# Digital_Output_B.net
KiCad netlist of a schematic drawn in EAGLE
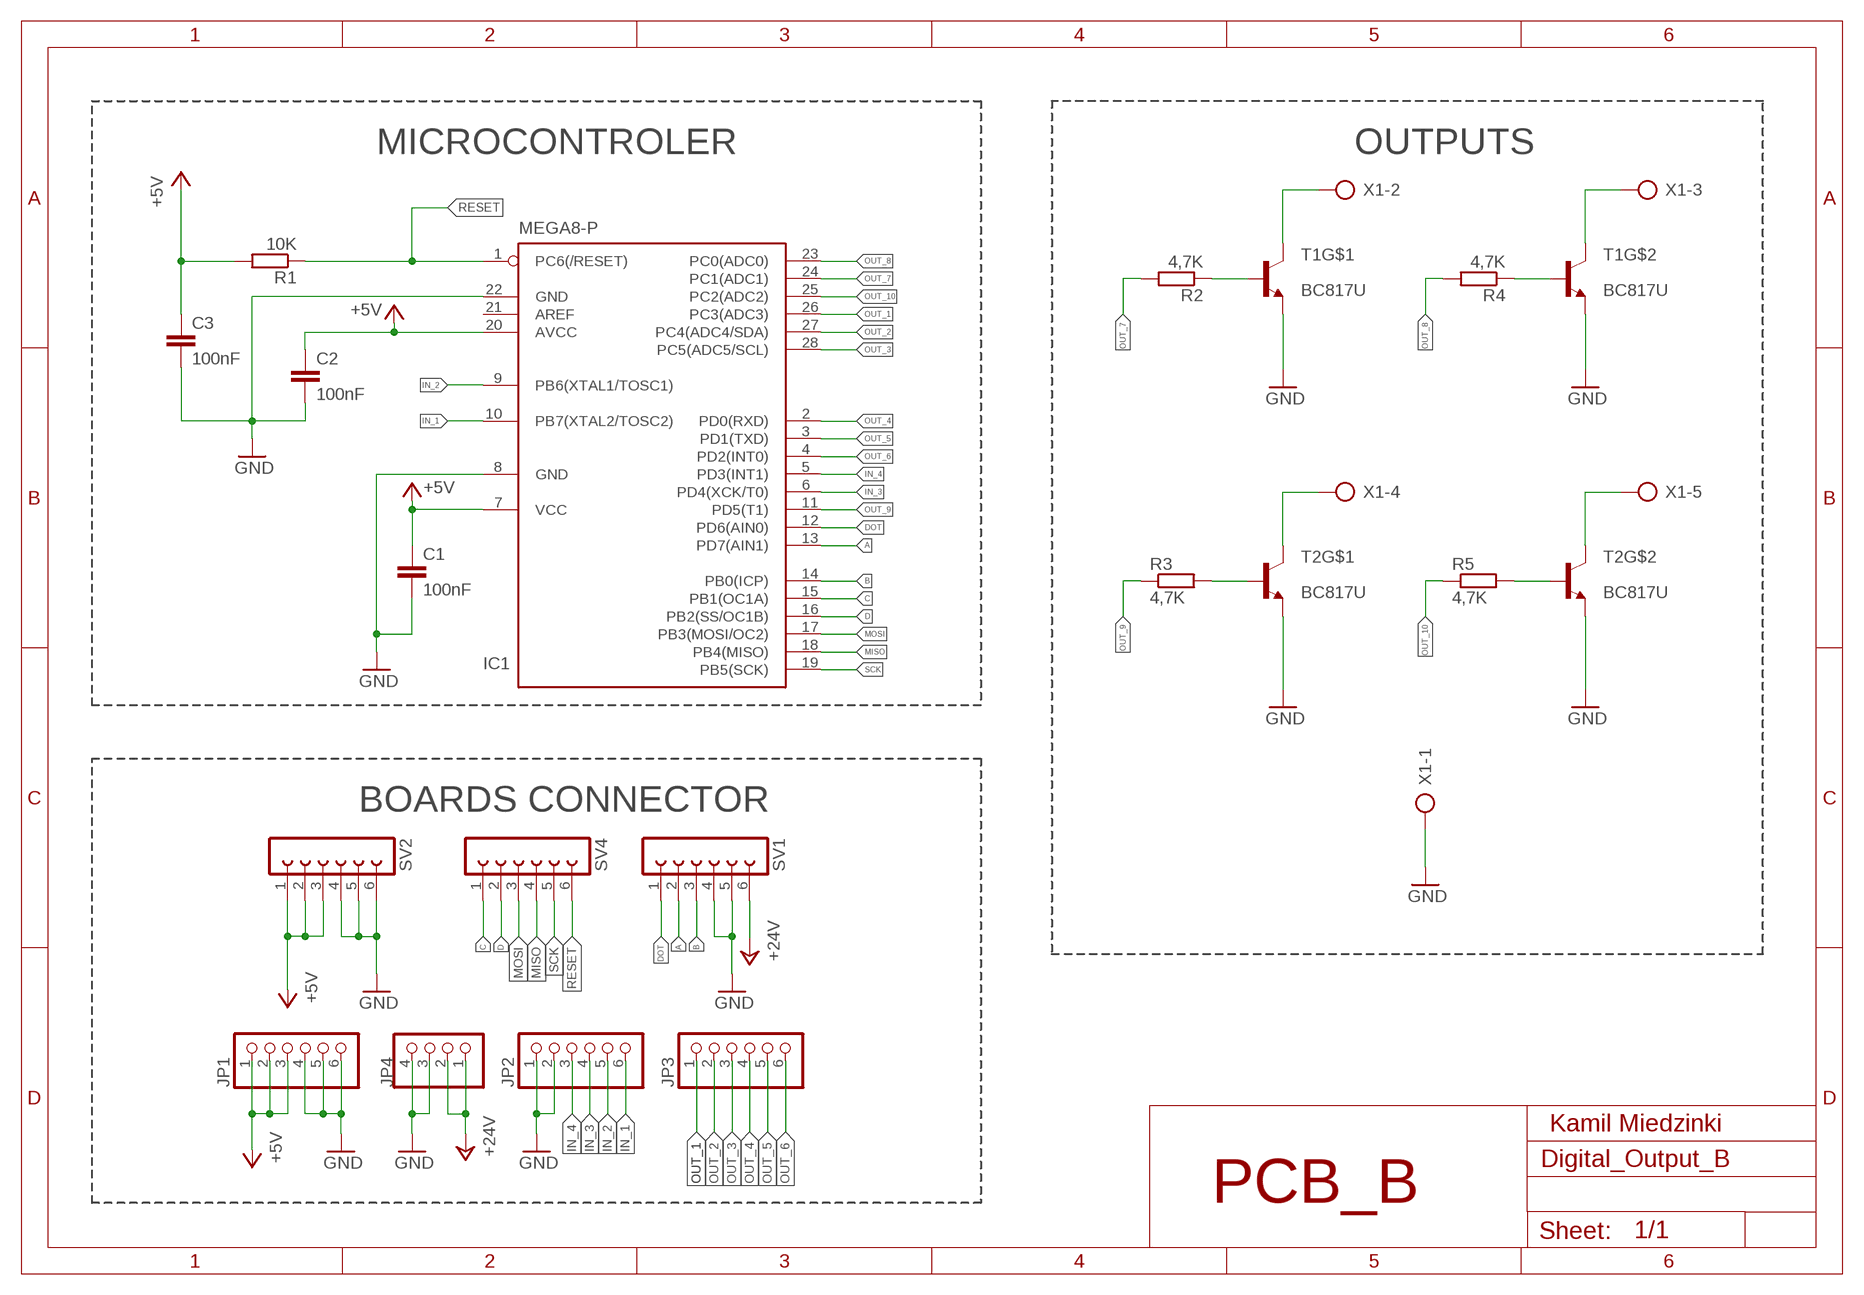
[diagram p0: schematic, sheet 1]

(export (version "E")
  (design (tool "Eeschema 10.0.6"))
  (components
    (comp (ref "C1")
      (value "100nF")
      (footprint "eagle-import:C0805K")
      (libsource (lib "eagle-import") (part "C-EUC0805K"))
    )
    (comp (ref "C2")
      (value "100nF")
      (footprint "eagle-import:C0805K")
      (libsource (lib "eagle-import") (part "C-EUC0805K"))
    )
    (comp (ref "C3")
      (value "100nF")
      (footprint "eagle-import:C0805K")
      (libsource (lib "eagle-import") (part "C-EUC0805K"))
    )
    (comp (ref "IC1")
      (value "MEGA8-P")
      (footprint "eagle-import:DIL28-3")
      (libsource (lib "eagle-import") (part "MEGA8-P"))
    )
    (comp (ref "JP1")
      (value "PINHD-1X6\"")
      (footprint "eagle-import:1X06H")
      (libsource (lib "eagle-import") (part "PINHD-1X6{dblquote}"))
    )
    (comp (ref "JP2")
      (value "PINHD-1X6\"")
      (footprint "eagle-import:1X06H")
      (libsource (lib "eagle-import") (part "PINHD-1X6{dblquote}"))
    )
    (comp (ref "JP3")
      (value "PINHD-1X6\"")
      (footprint "eagle-import:1X06H")
      (libsource (lib "eagle-import") (part "PINHD-1X6{dblquote}"))
    )
    (comp (ref "JP4")
      (value "PINHD-1X41X04H")
      (footprint "eagle-import:1X04H")
      (libsource (lib "eagle-import") (part "PINHD-1X41X04H"))
    )
    (comp (ref "R1")
      (value "10K")
      (footprint "eagle-import:R0805")
      (libsource (lib "eagle-import") (part "R-EU_R0805"))
    )
    (comp (ref "R2")
      (value "4,7K")
      (footprint "eagle-import:R0805")
      (libsource (lib "eagle-import") (part "R-EU_R0805"))
    )
    (comp (ref "R3")
      (value "4,7K")
      (footprint "eagle-import:R0805")
      (libsource (lib "eagle-import") (part "R-EU_R0805"))
    )
    (comp (ref "R4")
      (value "4,7K")
      (footprint "eagle-import:R0805")
      (libsource (lib "eagle-import") (part "R-EU_R0805"))
    )
    (comp (ref "R5")
      (value "4,7K")
      (footprint "eagle-import:R0805")
      (libsource (lib "eagle-import") (part "R-EU_R0805"))
    )
    (comp (ref "SV1")
      (value "FE06-1")
      (footprint "eagle-import:FE06")
      (libsource (lib "eagle-import") (part "FE06-1"))
    )
    (comp (ref "SV2")
      (value "FE06-1")
      (footprint "eagle-import:FE06")
      (libsource (lib "eagle-import") (part "FE06-1"))
    )
    (comp (ref "SV4")
      (value "FE06-1")
      (footprint "eagle-import:FE06")
      (libsource (lib "eagle-import") (part "FE06-1"))
    )
    (comp (ref "T1")
      (value "BC817U")
      (footprint "eagle-import:INF-SC74")
      (libsource (lib "eagle-import") (part "BC817U"))
    )
    (comp (ref "T2")
      (value "BC817U")
      (footprint "eagle-import:INF-SC74")
      (libsource (lib "eagle-import") (part "BC817U"))
    )
    (comp (ref "X1")
      (value "MKDS_3/5")
      (footprint "eagle-import:MKDS_3_5")
      (libsource (lib "eagle-import") (part "MKDS_3/5"))
    )
  )
  (nets
    (net (code "1") (name "+5V") (class "Default")
      (node (ref "C1") (pin "1") (pinfunction "1_1") (pintype "passive"))
      (node (ref "C2") (pin "1") (pinfunction "1_1") (pintype "passive"))
      (node (ref "C3") (pin "1") (pinfunction "1_1") (pintype "passive"))
      (node (ref "IC1") (pin "20") (pinfunction "AVCC_20") (pintype "power_in"))
      (node (ref "IC1") (pin "7") (pinfunction "VCC_7") (pintype "power_in"))
      (node (ref "JP1") (pin "1") (pinfunction "1_1") (pintype "passive"))
      (node (ref "JP1") (pin "2") (pinfunction "2_2") (pintype "passive"))
      (node (ref "JP1") (pin "3") (pinfunction "3_3") (pintype "passive"))
      (node (ref "R1") (pin "2") (pinfunction "2_2") (pintype "passive"))
      (node (ref "SV2") (pin "1") (pinfunction "1_1") (pintype "passive"))
      (node (ref "SV2") (pin "2") (pinfunction "2_2") (pintype "passive"))
      (node (ref "SV2") (pin "3") (pinfunction "3_3") (pintype "passive"))
    )
    (net (code "2") (name "+24V") (class "Default")
      (node (ref "JP4") (pin "1") (pinfunction "1_1") (pintype "passive"))
      (node (ref "JP4") (pin "2") (pinfunction "2_2") (pintype "passive"))
      (node (ref "SV1") (pin "6") (pinfunction "6_6") (pintype "passive"))
    )
    (net (code "3") (name "A") (class "Default")
      (node (ref "IC1") (pin "13") (pinfunction "PD7(AIN1)_13") (pintype "bidirectional"))
      (node (ref "SV1") (pin "2") (pinfunction "2_2") (pintype "passive"))
    )
    (net (code "4") (name "B") (class "Default")
      (node (ref "IC1") (pin "14") (pinfunction "PB0(ICP)_14") (pintype "bidirectional"))
      (node (ref "SV1") (pin "3") (pinfunction "3_3") (pintype "passive"))
    )
    (net (code "5") (name "C") (class "Default")
      (node (ref "IC1") (pin "15") (pinfunction "PB1(OC1A)_15") (pintype "bidirectional"))
      (node (ref "SV4") (pin "1") (pinfunction "1_1") (pintype "passive"))
    )
    (net (code "6") (name "D") (class "Default")
      (node (ref "IC1") (pin "16") (pinfunction "PB2(SS/OC1B)_16") (pintype "bidirectional"))
      (node (ref "SV4") (pin "2") (pinfunction "2_2") (pintype "passive"))
    )
    (net (code "7") (name "DOT") (class "Default")
      (node (ref "IC1") (pin "12") (pinfunction "PD6(AIN0)_12") (pintype "bidirectional"))
      (node (ref "SV1") (pin "1") (pinfunction "1_1") (pintype "passive"))
    )
    (net (code "8") (name "GND") (class "Default")
      (node (ref "C1") (pin "2") (pinfunction "2_2") (pintype "passive"))
      (node (ref "C2") (pin "2") (pinfunction "2_2") (pintype "passive"))
      (node (ref "C3") (pin "2") (pinfunction "2_2") (pintype "passive"))
      (node (ref "IC1") (pin "22") (pinfunction "GND_22") (pintype "power_in"))
      (node (ref "IC1") (pin "8") (pinfunction "GND_8") (pintype "power_in"))
      (node (ref "JP1") (pin "4") (pinfunction "4_4") (pintype "passive"))
      (node (ref "JP1") (pin "5") (pinfunction "5_5") (pintype "passive"))
      (node (ref "JP1") (pin "6") (pinfunction "6_6") (pintype "passive"))
      (node (ref "JP2") (pin "1") (pinfunction "1_1") (pintype "passive"))
      (node (ref "JP2") (pin "2") (pinfunction "2_2") (pintype "passive"))
      (node (ref "JP4") (pin "3") (pinfunction "3_3") (pintype "passive"))
      (node (ref "JP4") (pin "4") (pinfunction "4_4") (pintype "passive"))
      (node (ref "SV1") (pin "4") (pinfunction "4_4") (pintype "passive"))
      (node (ref "SV1") (pin "5") (pinfunction "5_5") (pintype "passive"))
      (node (ref "SV2") (pin "4") (pinfunction "4_4") (pintype "passive"))
      (node (ref "SV2") (pin "5") (pinfunction "5_5") (pintype "passive"))
      (node (ref "SV2") (pin "6") (pinfunction "6_6") (pintype "passive"))
      (node (ref "T1") (pin "1") (pinfunction "E_1") (pintype "passive"))
      (node (ref "T1") (pin "4") (pinfunction "E_4") (pintype "passive"))
      (node (ref "T2") (pin "1") (pinfunction "E_1") (pintype "passive"))
      (node (ref "T2") (pin "4") (pinfunction "E_4") (pintype "passive"))
      (node (ref "X1") (pin "1") (pinfunction "KL_1") (pintype "passive"))
    )
    (net (code "9") (name "IN_1") (class "Default")
      (node (ref "IC1") (pin "10") (pinfunction "PB7(XTAL2/TOSC2)_10") (pintype "bidirectional"))
      (node (ref "JP2") (pin "6") (pinfunction "6_6") (pintype "passive"))
    )
    (net (code "10") (name "IN_2") (class "Default")
      (node (ref "IC1") (pin "9") (pinfunction "PB6(XTAL1/TOSC1)_9") (pintype "bidirectional"))
      (node (ref "JP2") (pin "5") (pinfunction "5_5") (pintype "passive"))
    )
    (net (code "11") (name "IN_3") (class "Default")
      (node (ref "IC1") (pin "6") (pinfunction "PD4(XCK/T0)_6") (pintype "bidirectional"))
      (node (ref "JP2") (pin "4") (pinfunction "4_4") (pintype "passive"))
    )
    (net (code "12") (name "IN_4") (class "Default")
      (node (ref "IC1") (pin "5") (pinfunction "PD3(INT1)_5") (pintype "bidirectional"))
      (node (ref "JP2") (pin "3") (pinfunction "3_3") (pintype "passive"))
    )
    (net (code "13") (name "MISO") (class "Default")
      (node (ref "IC1") (pin "18") (pinfunction "PB4(MISO)_18") (pintype "bidirectional"))
      (node (ref "SV4") (pin "4") (pinfunction "4_4") (pintype "passive"))
    )
    (net (code "14") (name "MOSI") (class "Default")
      (node (ref "IC1") (pin "17") (pinfunction "PB3(MOSI/OC2)_17") (pintype "bidirectional"))
      (node (ref "SV4") (pin "3") (pinfunction "3_3") (pintype "passive"))
    )
    (net (code "15") (name "Net-(T1A-B)") (class "Default")
      (node (ref "R2") (pin "1") (pinfunction "1_1") (pintype "passive"))
      (node (ref "T1") (pin "2") (pinfunction "B_2") (pintype "passive"))
    )
    (net (code "16") (name "Net-(T1A-C)") (class "Default")
      (node (ref "T1") (pin "6") (pinfunction "C_6") (pintype "passive"))
      (node (ref "X1") (pin "2") (pinfunction "KL_2") (pintype "passive"))
    )
    (net (code "17") (name "Net-(T1B-B)") (class "Default")
      (node (ref "R4") (pin "1") (pinfunction "1_1") (pintype "passive"))
      (node (ref "T1") (pin "5") (pinfunction "B_5") (pintype "passive"))
    )
    (net (code "18") (name "Net-(T1B-C)") (class "Default")
      (node (ref "T1") (pin "3") (pinfunction "C_3") (pintype "passive"))
      (node (ref "X1") (pin "3") (pinfunction "KL_3") (pintype "passive"))
    )
    (net (code "19") (name "Net-(T2A-B)") (class "Default")
      (node (ref "R3") (pin "2") (pinfunction "2_2") (pintype "passive"))
      (node (ref "T2") (pin "2") (pinfunction "B_2") (pintype "passive"))
    )
    (net (code "20") (name "Net-(T2A-C)") (class "Default")
      (node (ref "T2") (pin "6") (pinfunction "C_6") (pintype "passive"))
      (node (ref "X1") (pin "4") (pinfunction "KL_4") (pintype "passive"))
    )
    (net (code "21") (name "Net-(T2B-B)") (class "Default")
      (node (ref "R5") (pin "2") (pinfunction "2_2") (pintype "passive"))
      (node (ref "T2") (pin "5") (pinfunction "B_5") (pintype "passive"))
    )
    (net (code "22") (name "Net-(T2B-C)") (class "Default")
      (node (ref "T2") (pin "3") (pinfunction "C_3") (pintype "passive"))
      (node (ref "X1") (pin "5") (pinfunction "KL_5") (pintype "passive"))
    )
    (net (code "23") (name "OUT_1") (class "Default")
      (node (ref "IC1") (pin "26") (pinfunction "PC3(ADC3)_26") (pintype "bidirectional"))
      (node (ref "JP3") (pin "1") (pinfunction "1_1") (pintype "passive"))
    )
    (net (code "24") (name "OUT_2") (class "Default")
      (node (ref "IC1") (pin "27") (pinfunction "PC4(ADC4/SDA)_27") (pintype "bidirectional"))
      (node (ref "JP3") (pin "2") (pinfunction "2_2") (pintype "passive"))
    )
    (net (code "25") (name "OUT_3") (class "Default")
      (node (ref "IC1") (pin "28") (pinfunction "PC5(ADC5/SCL)_28") (pintype "bidirectional"))
      (node (ref "JP3") (pin "3") (pinfunction "3_3") (pintype "passive"))
    )
    (net (code "26") (name "OUT_4") (class "Default")
      (node (ref "IC1") (pin "2") (pinfunction "PD0(RXD)_2") (pintype "bidirectional"))
      (node (ref "JP3") (pin "4") (pinfunction "4_4") (pintype "passive"))
    )
    (net (code "27") (name "OUT_5") (class "Default")
      (node (ref "IC1") (pin "3") (pinfunction "PD1(TXD)_3") (pintype "bidirectional"))
      (node (ref "JP3") (pin "5") (pinfunction "5_5") (pintype "passive"))
    )
    (net (code "28") (name "OUT_6") (class "Default")
      (node (ref "IC1") (pin "4") (pinfunction "PD2(INT0)_4") (pintype "bidirectional"))
      (node (ref "JP3") (pin "6") (pinfunction "6_6") (pintype "passive"))
    )
    (net (code "29") (name "OUT_7") (class "Default")
      (node (ref "IC1") (pin "24") (pinfunction "PC1(ADC1)_24") (pintype "bidirectional"))
      (node (ref "R2") (pin "2") (pinfunction "2_2") (pintype "passive"))
    )
    (net (code "30") (name "OUT_8") (class "Default")
      (node (ref "IC1") (pin "23") (pinfunction "PC0(ADC0)_23") (pintype "bidirectional"))
      (node (ref "R4") (pin "2") (pinfunction "2_2") (pintype "passive"))
    )
    (net (code "31") (name "OUT_9") (class "Default")
      (node (ref "IC1") (pin "11") (pinfunction "PD5(T1)_11") (pintype "bidirectional"))
      (node (ref "R3") (pin "1") (pinfunction "1_1") (pintype "passive"))
    )
    (net (code "32") (name "OUT_10") (class "Default")
      (node (ref "IC1") (pin "25") (pinfunction "PC2(ADC2)_25") (pintype "bidirectional"))
      (node (ref "R5") (pin "1") (pinfunction "1_1") (pintype "passive"))
    )
    (net (code "33") (name "RESET") (class "Default")
      (node (ref "IC1") (pin "1") (pinfunction "PC6(/RESET)_1") (pintype "bidirectional"))
      (node (ref "R1") (pin "1") (pinfunction "1_1") (pintype "passive"))
      (node (ref "SV4") (pin "6") (pinfunction "6_6") (pintype "passive"))
    )
    (net (code "34") (name "SCK") (class "Default")
      (node (ref "IC1") (pin "19") (pinfunction "PB5(SCK)_19") (pintype "bidirectional"))
      (node (ref "SV4") (pin "5") (pinfunction "5_5") (pintype "passive"))
    )
    (net (code "35") (name "unconnected-(IC1-AREF-Pad21)") (class "Default")
      (node (ref "IC1") (pin "21") (pinfunction "AREF_21") (pintype "passive"))
    )
  )
)
